# LogicBoard.net
KiCad netlist of a schematic drawn in EAGLE
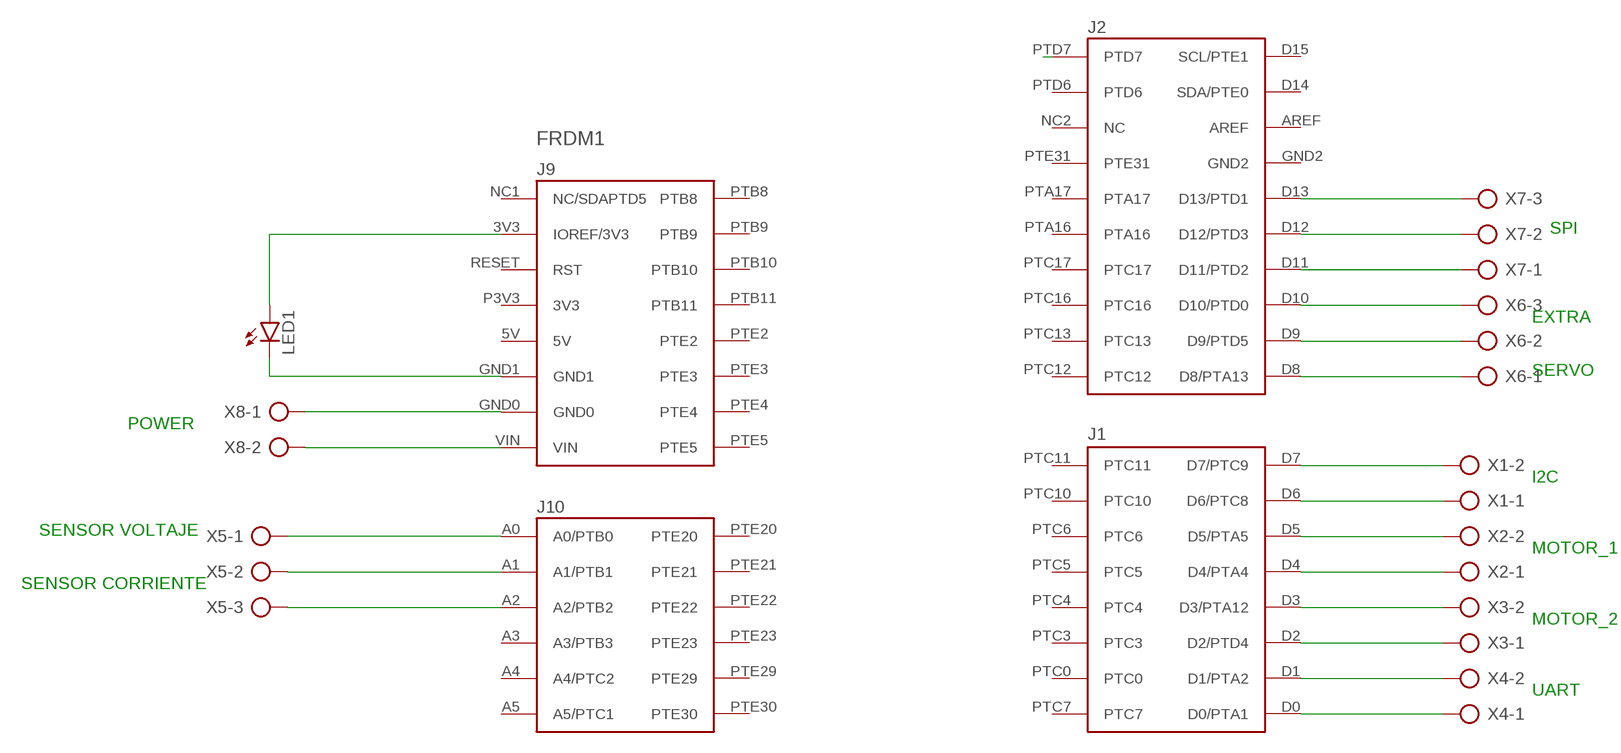
[diagram p0: schematic, sheet 1]

(export (version "E")
  (design (tool "Eeschema 10.0.6"))
  (components
    (comp (ref "FRDM1")
      (value "FRDM-KL25ZNORMAL")
      (footprint "eagle-import:FRDM_KL25Z_NORMAL")
      (fields (field (name "MF") "NXP USA") (field (name "MP") "FRDM-KL25Z"))
      (libsource (lib "eagle-import") (part "FRDM-KL25ZNORMAL"))
    )
    (comp (ref "LED1")
      (value "LED5MM")
      (footprint "eagle-import:LED5MM")
      (libsource (lib "eagle-import") (part "LED5MM"))
    )
    (comp (ref "X1")
      (value "AK500/2")
      (footprint "eagle-import:AK500_2")
      (libsource (lib "eagle-import") (part "AK500/2"))
    )
    (comp (ref "X2")
      (value "AK500/2")
      (footprint "eagle-import:AK500_2")
      (libsource (lib "eagle-import") (part "AK500/2"))
    )
    (comp (ref "X3")
      (value "AK500/2")
      (footprint "eagle-import:AK500_2")
      (libsource (lib "eagle-import") (part "AK500/2"))
    )
    (comp (ref "X4")
      (value "AK500/2")
      (footprint "eagle-import:AK500_2")
      (libsource (lib "eagle-import") (part "AK500/2"))
    )
    (comp (ref "X5")
      (value "AK500/3")
      (footprint "eagle-import:AK500_3")
      (libsource (lib "eagle-import") (part "AK500/3"))
    )
    (comp (ref "X6")
      (value "AK500/3")
      (footprint "eagle-import:AK500_3")
      (libsource (lib "eagle-import") (part "AK500/3"))
    )
    (comp (ref "X7")
      (value "AK500/3")
      (footprint "eagle-import:AK500_3")
      (libsource (lib "eagle-import") (part "AK500/3"))
    )
    (comp (ref "X8")
      (value "AK500/2")
      (footprint "eagle-import:AK500_2")
      (libsource (lib "eagle-import") (part "AK500/2"))
    )
  )
  (nets
    (net (code "1") (name "Net-(FRDM1-A0{slash}PTB0)") (class "Default")
      (node (ref "FRDM1") (pin "A0") (pinfunction "A0/PTB0_A0") (pintype "bidirectional"))
      (node (ref "X5") (pin "1") (pinfunction "KL_1") (pintype "passive"))
    )
    (net (code "2") (name "Net-(FRDM1-A1{slash}PTB1)") (class "Default")
      (node (ref "FRDM1") (pin "A1") (pinfunction "A1/PTB1_A1") (pintype "bidirectional"))
      (node (ref "X5") (pin "2") (pinfunction "KL_2") (pintype "passive"))
    )
    (net (code "3") (name "Net-(FRDM1-A2{slash}PTB2)") (class "Default")
      (node (ref "FRDM1") (pin "A2") (pinfunction "A2/PTB2_A2") (pintype "bidirectional"))
      (node (ref "X5") (pin "3") (pinfunction "KL_3") (pintype "passive"))
    )
    (net (code "4") (name "Net-(FRDM1-D0{slash}PTA1)") (class "Default")
      (node (ref "FRDM1") (pin "D0") (pinfunction "D0/PTA1_D0") (pintype "bidirectional"))
      (node (ref "X4") (pin "1") (pinfunction "KL_1") (pintype "passive"))
    )
    (net (code "5") (name "Net-(FRDM1-D1{slash}PTA2)") (class "Default")
      (node (ref "FRDM1") (pin "D1") (pinfunction "D1/PTA2_D1") (pintype "bidirectional"))
      (node (ref "X4") (pin "2") (pinfunction "KL_2") (pintype "passive"))
    )
    (net (code "6") (name "Net-(FRDM1-D2{slash}PTD4)") (class "Default")
      (node (ref "FRDM1") (pin "D2") (pinfunction "D2/PTD4_D2") (pintype "bidirectional"))
      (node (ref "X3") (pin "1") (pinfunction "KL_1") (pintype "passive"))
    )
    (net (code "7") (name "Net-(FRDM1-D3{slash}PTA12)") (class "Default")
      (node (ref "FRDM1") (pin "D3") (pinfunction "D3/PTA12_D3") (pintype "bidirectional"))
      (node (ref "X3") (pin "2") (pinfunction "KL_2") (pintype "passive"))
    )
    (net (code "8") (name "Net-(FRDM1-D4{slash}PTA4)") (class "Default")
      (node (ref "FRDM1") (pin "D4") (pinfunction "D4/PTA4_D4") (pintype "bidirectional"))
      (node (ref "X2") (pin "1") (pinfunction "KL_1") (pintype "passive"))
    )
    (net (code "9") (name "Net-(FRDM1-D5{slash}PTA5)") (class "Default")
      (node (ref "FRDM1") (pin "D5") (pinfunction "D5/PTA5_D5") (pintype "bidirectional"))
      (node (ref "X2") (pin "2") (pinfunction "KL_2") (pintype "passive"))
    )
    (net (code "10") (name "Net-(FRDM1-D6{slash}PTC8)") (class "Default")
      (node (ref "FRDM1") (pin "D6") (pinfunction "D6/PTC8_D6") (pintype "bidirectional"))
      (node (ref "X1") (pin "1") (pinfunction "KL_1") (pintype "passive"))
    )
    (net (code "11") (name "Net-(FRDM1-D7{slash}PTC9)") (class "Default")
      (node (ref "FRDM1") (pin "D7") (pinfunction "D7/PTC9_D7") (pintype "bidirectional"))
      (node (ref "X1") (pin "2") (pinfunction "KL_2") (pintype "passive"))
    )
    (net (code "12") (name "Net-(FRDM1-D8{slash}PTA13)") (class "Default")
      (node (ref "FRDM1") (pin "D8") (pinfunction "D8/PTA13_D8") (pintype "bidirectional"))
      (node (ref "X6") (pin "1") (pinfunction "KL_1") (pintype "passive"))
    )
    (net (code "13") (name "Net-(FRDM1-D9{slash}PTD5)") (class "Default")
      (node (ref "FRDM1") (pin "D9") (pinfunction "D9/PTD5_D9") (pintype "bidirectional"))
      (node (ref "X6") (pin "2") (pinfunction "KL_2") (pintype "passive"))
    )
    (net (code "14") (name "Net-(FRDM1-D10{slash}PTD0)") (class "Default")
      (node (ref "FRDM1") (pin "D10") (pinfunction "D10/PTD0_D10") (pintype "bidirectional"))
      (node (ref "X6") (pin "3") (pinfunction "KL_3") (pintype "passive"))
    )
    (net (code "15") (name "Net-(FRDM1-D11{slash}PTD2)") (class "Default")
      (node (ref "FRDM1") (pin "D11") (pinfunction "D11/PTD2_D11") (pintype "bidirectional"))
      (node (ref "X7") (pin "1") (pinfunction "KL_1") (pintype "passive"))
    )
    (net (code "16") (name "Net-(FRDM1-D12{slash}PTD3)") (class "Default")
      (node (ref "FRDM1") (pin "D12") (pinfunction "D12/PTD3_D12") (pintype "bidirectional"))
      (node (ref "X7") (pin "2") (pinfunction "KL_2") (pintype "passive"))
    )
    (net (code "17") (name "Net-(FRDM1-D13{slash}PTD1)") (class "Default")
      (node (ref "FRDM1") (pin "D13") (pinfunction "D13/PTD1_D13") (pintype "bidirectional"))
      (node (ref "X7") (pin "3") (pinfunction "KL_3") (pintype "passive"))
    )
    (net (code "18") (name "Net-(FRDM1-IOREF{slash}3V3)") (class "Default")
      (node (ref "FRDM1") (pin "3V3") (pinfunction "IOREF/3V3_3V3") (pintype "bidirectional"))
      (node (ref "LED1") (pin "A") (pinfunction "A_A") (pintype "passive"))
    )
    (net (code "19") (name "Net-(LED1-C)") (class "Default")
      (node (ref "FRDM1") (pin "GND1") (pinfunction "GND1_GND1") (pintype "bidirectional"))
      (node (ref "LED1") (pin "K") (pinfunction "C_K") (pintype "passive"))
    )
    (net (code "20") (name "Net-(X8A-KL)") (class "Default")
      (node (ref "FRDM1") (pin "GND0") (pinfunction "GND0_GND0") (pintype "bidirectional"))
      (node (ref "X8") (pin "1") (pinfunction "KL_1") (pintype "passive"))
    )
    (net (code "21") (name "Net-(X8B-KL)") (class "Default")
      (node (ref "FRDM1") (pin "VIN") (pinfunction "VIN_VIN") (pintype "bidirectional"))
      (node (ref "X8") (pin "2") (pinfunction "KL_2") (pintype "passive"))
    )
    (net (code "22") (name "unconnected-(FRDM1-3V3-PadP3V3)") (class "Default")
      (node (ref "FRDM1") (pin "P3V3") (pinfunction "3V3_P3V3") (pintype "bidirectional"))
    )
    (net (code "23") (name "unconnected-(FRDM1-A3{slash}PTB3-PadA3)") (class "Default")
      (node (ref "FRDM1") (pin "A3") (pinfunction "A3/PTB3_A3") (pintype "bidirectional"))
    )
    (net (code "24") (name "unconnected-(FRDM1-A4{slash}PTC2-PadA4)") (class "Default")
      (node (ref "FRDM1") (pin "A4") (pinfunction "A4/PTC2_A4") (pintype "bidirectional"))
    )
    (net (code "25") (name "unconnected-(FRDM1-A5{slash}PTC1-PadA5)") (class "Default")
      (node (ref "FRDM1") (pin "A5") (pinfunction "A5/PTC1_A5") (pintype "bidirectional"))
    )
    (net (code "26") (name "unconnected-(FRDM1-NC-PadNC2)") (class "Default")
      (node (ref "FRDM1") (pin "NC2") (pinfunction "NC_NC2") (pintype "bidirectional"))
    )
    (net (code "27") (name "unconnected-(FRDM1-NC{slash}SDAPTD5-PadNC1)") (class "Default")
      (node (ref "FRDM1") (pin "NC1") (pinfunction "NC/SDAPTD5_NC1") (pintype "bidirectional"))
    )
    (net (code "28") (name "unconnected-(FRDM1-Pad5V)") (class "Default")
      (node (ref "FRDM1") (pin "5V") (pinfunction "5V_5V") (pintype "bidirectional"))
    )
    (net (code "29") (name "unconnected-(FRDM1-PadAREF)") (class "Default")
      (node (ref "FRDM1") (pin "AREF") (pinfunction "AREF_AREF") (pintype "bidirectional"))
    )
    (net (code "30") (name "unconnected-(FRDM1-PadGND2)") (class "Default")
      (node (ref "FRDM1") (pin "GND2") (pinfunction "GND2_GND2") (pintype "bidirectional"))
    )
    (net (code "31") (name "unconnected-(FRDM1-PadPTA16)") (class "Default")
      (node (ref "FRDM1") (pin "PTA16") (pinfunction "PTA16_PTA16") (pintype "bidirectional"))
    )
    (net (code "32") (name "unconnected-(FRDM1-PadPTA17)") (class "Default")
      (node (ref "FRDM1") (pin "PTA17") (pinfunction "PTA17_PTA17") (pintype "bidirectional"))
    )
    (net (code "33") (name "unconnected-(FRDM1-PadPTB8)") (class "Default")
      (node (ref "FRDM1") (pin "PTB8") (pinfunction "PTB8_PTB8") (pintype "bidirectional"))
    )
    (net (code "34") (name "unconnected-(FRDM1-PadPTB9)") (class "Default")
      (node (ref "FRDM1") (pin "PTB9") (pinfunction "PTB9_PTB9") (pintype "bidirectional"))
    )
    (net (code "35") (name "unconnected-(FRDM1-PadPTB10)") (class "Default")
      (node (ref "FRDM1") (pin "PTB10") (pinfunction "PTB10_PTB10") (pintype "bidirectional"))
    )
    (net (code "36") (name "unconnected-(FRDM1-PadPTB11)") (class "Default")
      (node (ref "FRDM1") (pin "PTB11") (pinfunction "PTB11_PTB11") (pintype "bidirectional"))
    )
    (net (code "37") (name "unconnected-(FRDM1-PadPTC0)") (class "Default")
      (node (ref "FRDM1") (pin "PTC0") (pinfunction "PTC0_PTC0") (pintype "bidirectional"))
    )
    (net (code "38") (name "unconnected-(FRDM1-PadPTC3)") (class "Default")
      (node (ref "FRDM1") (pin "PTC3") (pinfunction "PTC3_PTC3") (pintype "bidirectional"))
    )
    (net (code "39") (name "unconnected-(FRDM1-PadPTC4)") (class "Default")
      (node (ref "FRDM1") (pin "PTC4") (pinfunction "PTC4_PTC4") (pintype "bidirectional"))
    )
    (net (code "40") (name "unconnected-(FRDM1-PadPTC5)") (class "Default")
      (node (ref "FRDM1") (pin "PTC5") (pinfunction "PTC5_PTC5") (pintype "bidirectional"))
    )
    (net (code "41") (name "unconnected-(FRDM1-PadPTC6)") (class "Default")
      (node (ref "FRDM1") (pin "PTC6") (pinfunction "PTC6_PTC6") (pintype "bidirectional"))
    )
    (net (code "42") (name "unconnected-(FRDM1-PadPTC7)") (class "Default")
      (node (ref "FRDM1") (pin "PTC7") (pinfunction "PTC7_PTC7") (pintype "bidirectional"))
    )
    (net (code "43") (name "unconnected-(FRDM1-PadPTC10)") (class "Default")
      (node (ref "FRDM1") (pin "PTC10") (pinfunction "PTC10_PTC10") (pintype "bidirectional"))
    )
    (net (code "44") (name "unconnected-(FRDM1-PadPTC11)") (class "Default")
      (node (ref "FRDM1") (pin "PTC11") (pinfunction "PTC11_PTC11") (pintype "bidirectional"))
    )
    (net (code "45") (name "unconnected-(FRDM1-PadPTC12)") (class "Default")
      (node (ref "FRDM1") (pin "PTC12") (pinfunction "PTC12_PTC12") (pintype "bidirectional"))
    )
    (net (code "46") (name "unconnected-(FRDM1-PadPTC13)") (class "Default")
      (node (ref "FRDM1") (pin "PTC13") (pinfunction "PTC13_PTC13") (pintype "bidirectional"))
    )
    (net (code "47") (name "unconnected-(FRDM1-PadPTC16)") (class "Default")
      (node (ref "FRDM1") (pin "PTC16") (pinfunction "PTC16_PTC16") (pintype "bidirectional"))
    )
    (net (code "48") (name "unconnected-(FRDM1-PadPTC17)") (class "Default")
      (node (ref "FRDM1") (pin "PTC17") (pinfunction "PTC17_PTC17") (pintype "bidirectional"))
    )
    (net (code "49") (name "unconnected-(FRDM1-PadPTD6)") (class "Default")
      (node (ref "FRDM1") (pin "PTD6") (pinfunction "PTD6_PTD6") (pintype "bidirectional"))
    )
    (net (code "50") (name "unconnected-(FRDM1-PadPTD7)") (class "Default")
      (node (ref "FRDM1") (pin "PTD7") (pinfunction "PTD7_PTD7") (pintype "bidirectional"))
    )
    (net (code "51") (name "unconnected-(FRDM1-PadPTE2)") (class "Default")
      (node (ref "FRDM1") (pin "PTE2") (pinfunction "PTE2_PTE2") (pintype "bidirectional"))
    )
    (net (code "52") (name "unconnected-(FRDM1-PadPTE3)") (class "Default")
      (node (ref "FRDM1") (pin "PTE3") (pinfunction "PTE3_PTE3") (pintype "bidirectional"))
    )
    (net (code "53") (name "unconnected-(FRDM1-PadPTE4)") (class "Default")
      (node (ref "FRDM1") (pin "PTE4") (pinfunction "PTE4_PTE4") (pintype "bidirectional"))
    )
    (net (code "54") (name "unconnected-(FRDM1-PadPTE5)") (class "Default")
      (node (ref "FRDM1") (pin "PTE5") (pinfunction "PTE5_PTE5") (pintype "bidirectional"))
    )
    (net (code "55") (name "unconnected-(FRDM1-PadPTE20)") (class "Default")
      (node (ref "FRDM1") (pin "PTE20") (pinfunction "PTE20_PTE20") (pintype "bidirectional"))
    )
    (net (code "56") (name "unconnected-(FRDM1-PadPTE21)") (class "Default")
      (node (ref "FRDM1") (pin "PTE21") (pinfunction "PTE21_PTE21") (pintype "bidirectional"))
    )
    (net (code "57") (name "unconnected-(FRDM1-PadPTE22)") (class "Default")
      (node (ref "FRDM1") (pin "PTE22") (pinfunction "PTE22_PTE22") (pintype "bidirectional"))
    )
    (net (code "58") (name "unconnected-(FRDM1-PadPTE23)") (class "Default")
      (node (ref "FRDM1") (pin "PTE23") (pinfunction "PTE23_PTE23") (pintype "bidirectional"))
    )
    (net (code "59") (name "unconnected-(FRDM1-PadPTE29)") (class "Default")
      (node (ref "FRDM1") (pin "PTE29") (pinfunction "PTE29_PTE29") (pintype "bidirectional"))
    )
    (net (code "60") (name "unconnected-(FRDM1-PadPTE30)") (class "Default")
      (node (ref "FRDM1") (pin "PTE30") (pinfunction "PTE30_PTE30") (pintype "bidirectional"))
    )
    (net (code "61") (name "unconnected-(FRDM1-PadPTE31)") (class "Default")
      (node (ref "FRDM1") (pin "PTE31") (pinfunction "PTE31_PTE31") (pintype "bidirectional"))
    )
    (net (code "62") (name "unconnected-(FRDM1-RST-PadRESET)") (class "Default")
      (node (ref "FRDM1") (pin "RESET") (pinfunction "RST_RESET") (pintype "bidirectional"))
    )
    (net (code "63") (name "unconnected-(FRDM1-SCL{slash}PTE1-PadD15)") (class "Default")
      (node (ref "FRDM1") (pin "D15") (pinfunction "SCL/PTE1_D15") (pintype "bidirectional"))
    )
    (net (code "64") (name "unconnected-(FRDM1-SDA{slash}PTE0-PadD14)") (class "Default")
      (node (ref "FRDM1") (pin "D14") (pinfunction "SDA/PTE0_D14") (pintype "bidirectional"))
    )
  )
)
